# 3way_d-sub.net
KiCad netlist of a schematic drawn in EAGLE
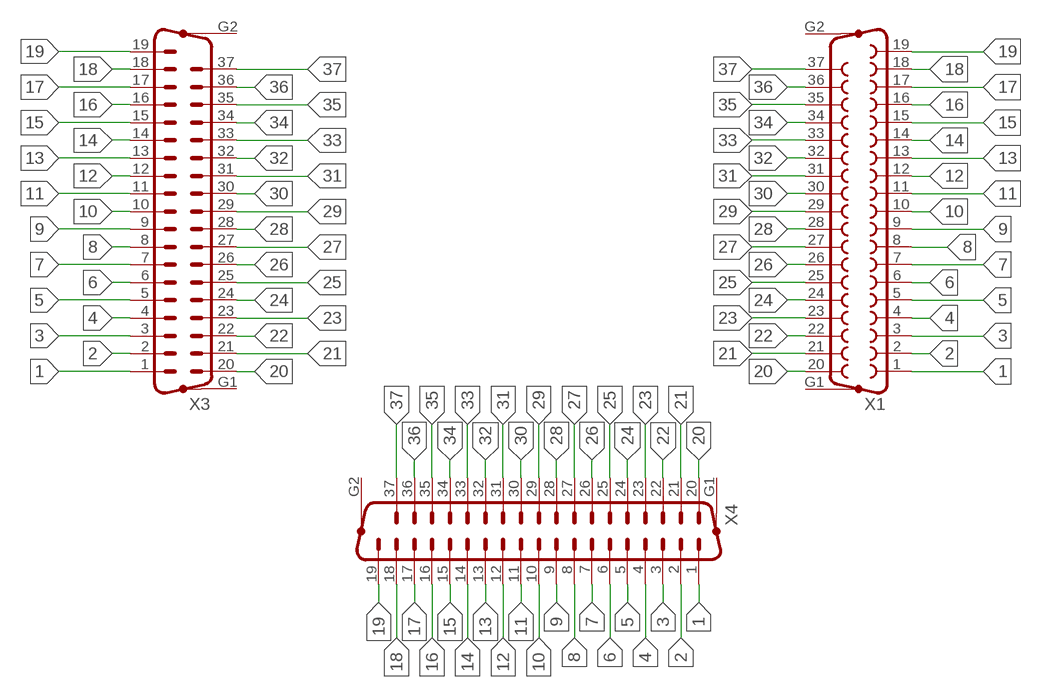
[diagram p0: schematic, sheet 1]

(export (version "E")
  (design (tool "Eeschema 10.0.6"))
  (components
    (comp (ref "X1")
      (value "F37HP")
      (footprint "eagle-import:F37HP")
      (libsource (lib "eagle-import") (part "F37HP"))
    )
    (comp (ref "X3")
      (value "M37HP")
      (footprint "eagle-import:M37HP")
      (libsource (lib "eagle-import") (part "M37HP"))
    )
    (comp (ref "X4")
      (value "M37HP")
      (footprint "eagle-import:M37HP")
      (libsource (lib "eagle-import") (part "M37HP"))
    )
  )
  (nets
    (net (code "1") (name "1") (class "Default")
      (node (ref "X1") (pin "1") (pinfunction "1_1") (pintype "passive"))
      (node (ref "X3") (pin "1") (pinfunction "1_1") (pintype "passive"))
      (node (ref "X4") (pin "1") (pinfunction "1_1") (pintype "passive"))
    )
    (net (code "2") (name "2") (class "Default")
      (node (ref "X1") (pin "2") (pinfunction "2_2") (pintype "passive"))
      (node (ref "X3") (pin "2") (pinfunction "2_2") (pintype "passive"))
      (node (ref "X4") (pin "2") (pinfunction "2_2") (pintype "passive"))
    )
    (net (code "3") (name "3") (class "Default")
      (node (ref "X1") (pin "3") (pinfunction "3_3") (pintype "passive"))
      (node (ref "X3") (pin "3") (pinfunction "3_3") (pintype "passive"))
      (node (ref "X4") (pin "3") (pinfunction "3_3") (pintype "passive"))
    )
    (net (code "4") (name "4") (class "Default")
      (node (ref "X1") (pin "4") (pinfunction "4_4") (pintype "passive"))
      (node (ref "X3") (pin "4") (pinfunction "4_4") (pintype "passive"))
      (node (ref "X4") (pin "4") (pinfunction "4_4") (pintype "passive"))
    )
    (net (code "5") (name "5") (class "Default")
      (node (ref "X1") (pin "5") (pinfunction "5_5") (pintype "passive"))
      (node (ref "X3") (pin "5") (pinfunction "5_5") (pintype "passive"))
      (node (ref "X4") (pin "5") (pinfunction "5_5") (pintype "passive"))
    )
    (net (code "6") (name "6") (class "Default")
      (node (ref "X1") (pin "6") (pinfunction "6_6") (pintype "passive"))
      (node (ref "X3") (pin "6") (pinfunction "6_6") (pintype "passive"))
      (node (ref "X4") (pin "6") (pinfunction "6_6") (pintype "passive"))
    )
    (net (code "7") (name "7") (class "Default")
      (node (ref "X1") (pin "7") (pinfunction "7_7") (pintype "passive"))
      (node (ref "X3") (pin "7") (pinfunction "7_7") (pintype "passive"))
      (node (ref "X4") (pin "7") (pinfunction "7_7") (pintype "passive"))
    )
    (net (code "8") (name "8") (class "Default")
      (node (ref "X1") (pin "8") (pinfunction "8_8") (pintype "passive"))
      (node (ref "X3") (pin "8") (pinfunction "8_8") (pintype "passive"))
      (node (ref "X4") (pin "8") (pinfunction "8_8") (pintype "passive"))
    )
    (net (code "9") (name "9") (class "Default")
      (node (ref "X1") (pin "9") (pinfunction "9_9") (pintype "passive"))
      (node (ref "X3") (pin "9") (pinfunction "9_9") (pintype "passive"))
      (node (ref "X4") (pin "9") (pinfunction "9_9") (pintype "passive"))
    )
    (net (code "10") (name "10") (class "Default")
      (node (ref "X1") (pin "10") (pinfunction "10_10") (pintype "passive"))
      (node (ref "X3") (pin "10") (pinfunction "10_10") (pintype "passive"))
      (node (ref "X4") (pin "10") (pinfunction "10_10") (pintype "passive"))
    )
    (net (code "11") (name "11") (class "Default")
      (node (ref "X1") (pin "11") (pinfunction "11_11") (pintype "passive"))
      (node (ref "X3") (pin "11") (pinfunction "11_11") (pintype "passive"))
      (node (ref "X4") (pin "11") (pinfunction "11_11") (pintype "passive"))
    )
    (net (code "12") (name "12") (class "Default")
      (node (ref "X1") (pin "12") (pinfunction "12_12") (pintype "passive"))
      (node (ref "X3") (pin "12") (pinfunction "12_12") (pintype "passive"))
      (node (ref "X4") (pin "12") (pinfunction "12_12") (pintype "passive"))
    )
    (net (code "13") (name "13") (class "Default")
      (node (ref "X1") (pin "13") (pinfunction "13_13") (pintype "passive"))
      (node (ref "X3") (pin "13") (pinfunction "13_13") (pintype "passive"))
      (node (ref "X4") (pin "13") (pinfunction "13_13") (pintype "passive"))
    )
    (net (code "14") (name "14") (class "Default")
      (node (ref "X1") (pin "14") (pinfunction "14_14") (pintype "passive"))
      (node (ref "X3") (pin "14") (pinfunction "14_14") (pintype "passive"))
      (node (ref "X4") (pin "14") (pinfunction "14_14") (pintype "passive"))
    )
    (net (code "15") (name "15") (class "Default")
      (node (ref "X1") (pin "15") (pinfunction "15_15") (pintype "passive"))
      (node (ref "X3") (pin "15") (pinfunction "15_15") (pintype "passive"))
      (node (ref "X4") (pin "15") (pinfunction "15_15") (pintype "passive"))
    )
    (net (code "16") (name "16") (class "Default")
      (node (ref "X1") (pin "16") (pinfunction "16_16") (pintype "passive"))
      (node (ref "X3") (pin "16") (pinfunction "16_16") (pintype "passive"))
      (node (ref "X4") (pin "16") (pinfunction "16_16") (pintype "passive"))
    )
    (net (code "17") (name "17") (class "Default")
      (node (ref "X1") (pin "17") (pinfunction "17_17") (pintype "passive"))
      (node (ref "X3") (pin "17") (pinfunction "17_17") (pintype "passive"))
      (node (ref "X4") (pin "17") (pinfunction "17_17") (pintype "passive"))
    )
    (net (code "18") (name "18") (class "Default")
      (node (ref "X1") (pin "18") (pinfunction "18_18") (pintype "passive"))
      (node (ref "X3") (pin "18") (pinfunction "18_18") (pintype "passive"))
      (node (ref "X4") (pin "18") (pinfunction "18_18") (pintype "passive"))
    )
    (net (code "19") (name "19") (class "Default")
      (node (ref "X1") (pin "19") (pinfunction "19_19") (pintype "passive"))
      (node (ref "X3") (pin "19") (pinfunction "19_19") (pintype "passive"))
      (node (ref "X4") (pin "19") (pinfunction "19_19") (pintype "passive"))
    )
    (net (code "20") (name "20") (class "Default")
      (node (ref "X1") (pin "20") (pinfunction "20_20") (pintype "passive"))
      (node (ref "X3") (pin "20") (pinfunction "20_20") (pintype "passive"))
      (node (ref "X4") (pin "20") (pinfunction "20_20") (pintype "passive"))
    )
    (net (code "21") (name "21") (class "Default")
      (node (ref "X1") (pin "21") (pinfunction "21_21") (pintype "passive"))
      (node (ref "X3") (pin "21") (pinfunction "21_21") (pintype "passive"))
      (node (ref "X4") (pin "21") (pinfunction "21_21") (pintype "passive"))
    )
    (net (code "22") (name "22") (class "Default")
      (node (ref "X1") (pin "22") (pinfunction "22_22") (pintype "passive"))
      (node (ref "X3") (pin "22") (pinfunction "22_22") (pintype "passive"))
      (node (ref "X4") (pin "22") (pinfunction "22_22") (pintype "passive"))
    )
    (net (code "23") (name "23") (class "Default")
      (node (ref "X1") (pin "23") (pinfunction "23_23") (pintype "passive"))
      (node (ref "X3") (pin "23") (pinfunction "23_23") (pintype "passive"))
      (node (ref "X4") (pin "23") (pinfunction "23_23") (pintype "passive"))
    )
    (net (code "24") (name "24") (class "Default")
      (node (ref "X1") (pin "24") (pinfunction "24_24") (pintype "passive"))
      (node (ref "X3") (pin "24") (pinfunction "24_24") (pintype "passive"))
      (node (ref "X4") (pin "24") (pinfunction "24_24") (pintype "passive"))
    )
    (net (code "25") (name "25") (class "Default")
      (node (ref "X1") (pin "25") (pinfunction "25_25") (pintype "passive"))
      (node (ref "X3") (pin "25") (pinfunction "25_25") (pintype "passive"))
      (node (ref "X4") (pin "25") (pinfunction "25_25") (pintype "passive"))
    )
    (net (code "26") (name "26") (class "Default")
      (node (ref "X1") (pin "26") (pinfunction "26_26") (pintype "passive"))
      (node (ref "X3") (pin "26") (pinfunction "26_26") (pintype "passive"))
      (node (ref "X4") (pin "26") (pinfunction "26_26") (pintype "passive"))
    )
    (net (code "27") (name "27") (class "Default")
      (node (ref "X1") (pin "27") (pinfunction "27_27") (pintype "passive"))
      (node (ref "X3") (pin "27") (pinfunction "27_27") (pintype "passive"))
      (node (ref "X4") (pin "27") (pinfunction "27_27") (pintype "passive"))
    )
    (net (code "28") (name "28") (class "Default")
      (node (ref "X1") (pin "28") (pinfunction "28_28") (pintype "passive"))
      (node (ref "X3") (pin "28") (pinfunction "28_28") (pintype "passive"))
      (node (ref "X4") (pin "28") (pinfunction "28_28") (pintype "passive"))
    )
    (net (code "29") (name "29") (class "Default")
      (node (ref "X1") (pin "29") (pinfunction "29_29") (pintype "passive"))
      (node (ref "X3") (pin "29") (pinfunction "29_29") (pintype "passive"))
      (node (ref "X4") (pin "29") (pinfunction "29_29") (pintype "passive"))
    )
    (net (code "30") (name "30") (class "Default")
      (node (ref "X1") (pin "30") (pinfunction "30_30") (pintype "passive"))
      (node (ref "X3") (pin "30") (pinfunction "30_30") (pintype "passive"))
      (node (ref "X4") (pin "30") (pinfunction "30_30") (pintype "passive"))
    )
    (net (code "31") (name "31") (class "Default")
      (node (ref "X1") (pin "31") (pinfunction "31_31") (pintype "passive"))
      (node (ref "X3") (pin "31") (pinfunction "31_31") (pintype "passive"))
      (node (ref "X4") (pin "31") (pinfunction "31_31") (pintype "passive"))
    )
    (net (code "32") (name "32") (class "Default")
      (node (ref "X1") (pin "32") (pinfunction "32_32") (pintype "passive"))
      (node (ref "X3") (pin "32") (pinfunction "32_32") (pintype "passive"))
      (node (ref "X4") (pin "32") (pinfunction "32_32") (pintype "passive"))
    )
    (net (code "33") (name "33") (class "Default")
      (node (ref "X1") (pin "33") (pinfunction "33_33") (pintype "passive"))
      (node (ref "X3") (pin "33") (pinfunction "33_33") (pintype "passive"))
      (node (ref "X4") (pin "33") (pinfunction "33_33") (pintype "passive"))
    )
    (net (code "34") (name "34") (class "Default")
      (node (ref "X1") (pin "34") (pinfunction "34_34") (pintype "passive"))
      (node (ref "X3") (pin "34") (pinfunction "34_34") (pintype "passive"))
      (node (ref "X4") (pin "34") (pinfunction "34_34") (pintype "passive"))
    )
    (net (code "35") (name "35") (class "Default")
      (node (ref "X1") (pin "35") (pinfunction "35_35") (pintype "passive"))
      (node (ref "X3") (pin "35") (pinfunction "35_35") (pintype "passive"))
      (node (ref "X4") (pin "35") (pinfunction "35_35") (pintype "passive"))
    )
    (net (code "36") (name "36") (class "Default")
      (node (ref "X1") (pin "36") (pinfunction "36_36") (pintype "passive"))
      (node (ref "X3") (pin "36") (pinfunction "36_36") (pintype "passive"))
      (node (ref "X4") (pin "36") (pinfunction "36_36") (pintype "passive"))
    )
    (net (code "37") (name "37") (class "Default")
      (node (ref "X1") (pin "37") (pinfunction "37_37") (pintype "passive"))
      (node (ref "X3") (pin "37") (pinfunction "37_37") (pintype "passive"))
      (node (ref "X4") (pin "37") (pinfunction "37_37") (pintype "passive"))
    )
    (net (code "38") (name "unconnected-(X1-PadG1)") (class "Default")
      (node (ref "X1") (pin "G1") (pinfunction "G1_G1") (pintype "passive"))
    )
    (net (code "39") (name "unconnected-(X1-PadG2)") (class "Default")
      (node (ref "X1") (pin "G2") (pinfunction "G2_G2") (pintype "passive"))
    )
    (net (code "40") (name "unconnected-(X3-PadG1)") (class "Default")
      (node (ref "X3") (pin "G1") (pinfunction "G1_G1") (pintype "passive"))
    )
    (net (code "41") (name "unconnected-(X3-PadG2)") (class "Default")
      (node (ref "X3") (pin "G2") (pinfunction "G2_G2") (pintype "passive"))
    )
    (net (code "42") (name "unconnected-(X4-PadG1)") (class "Default")
      (node (ref "X4") (pin "G1") (pinfunction "G1_G1") (pintype "passive"))
    )
    (net (code "43") (name "unconnected-(X4-PadG2)") (class "Default")
      (node (ref "X4") (pin "G2") (pinfunction "G2_G2") (pintype "passive"))
    )
  )
)
